# ESP32_With_USB-C_Port_AL.net
KiCad netlist of a schematic drawn in Altium Designer
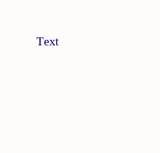
[diagram p0: ESP32_With_USB-C_Port_AL.SchDoc, top left]
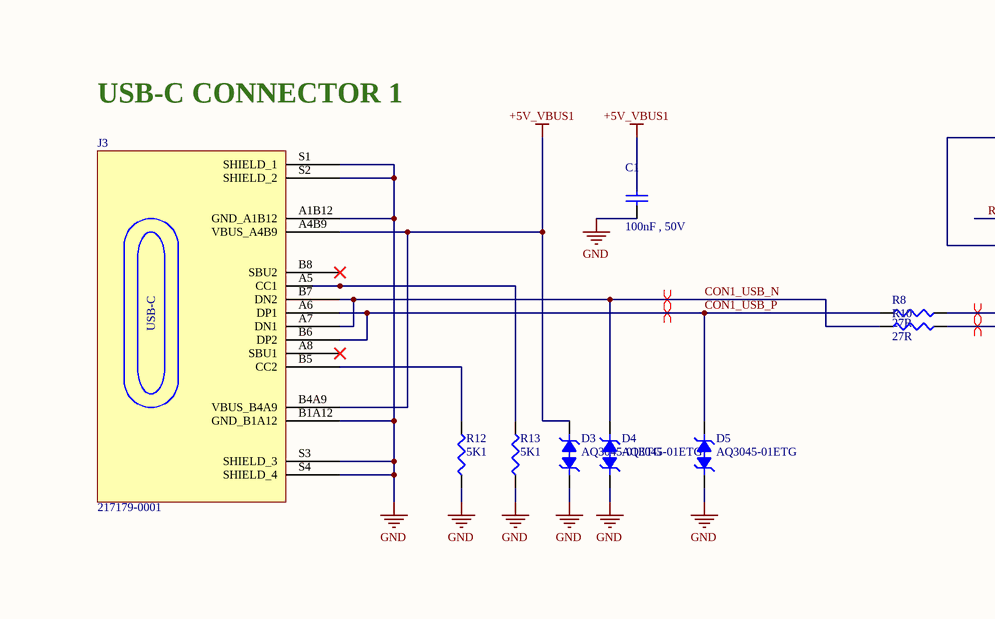
[diagram p1: ESP32_With_USB-C_Port_AL.SchDoc, top middle]
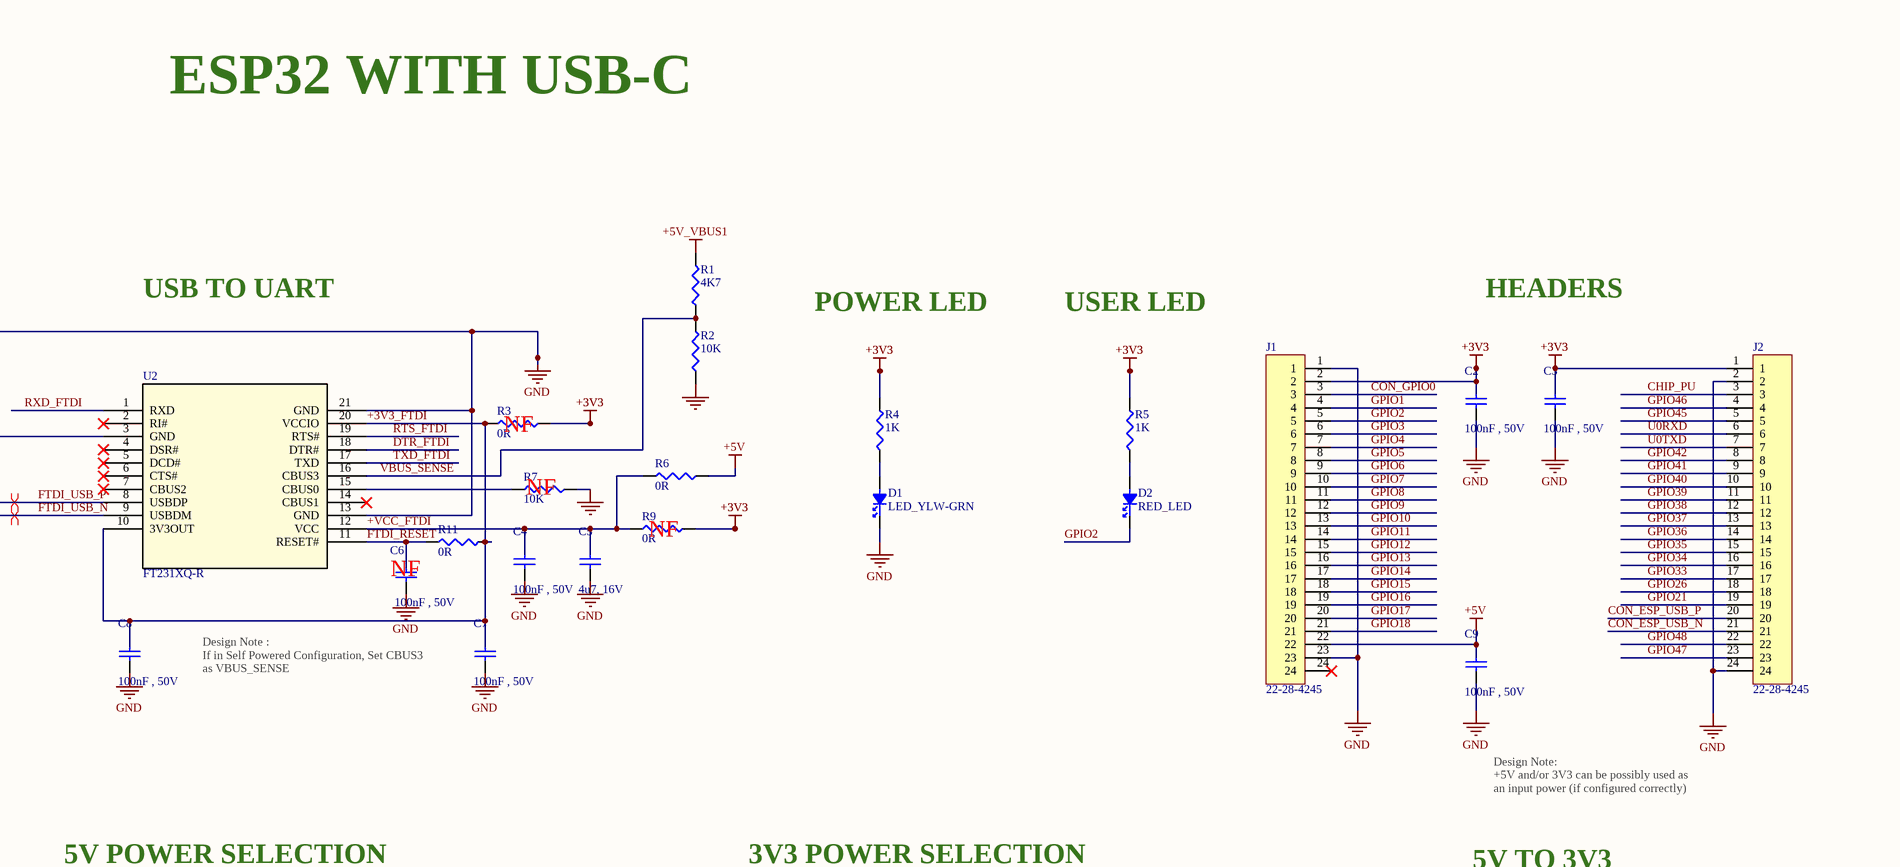
[diagram p2: ESP32_With_USB-C_Port_AL.SchDoc, top right]
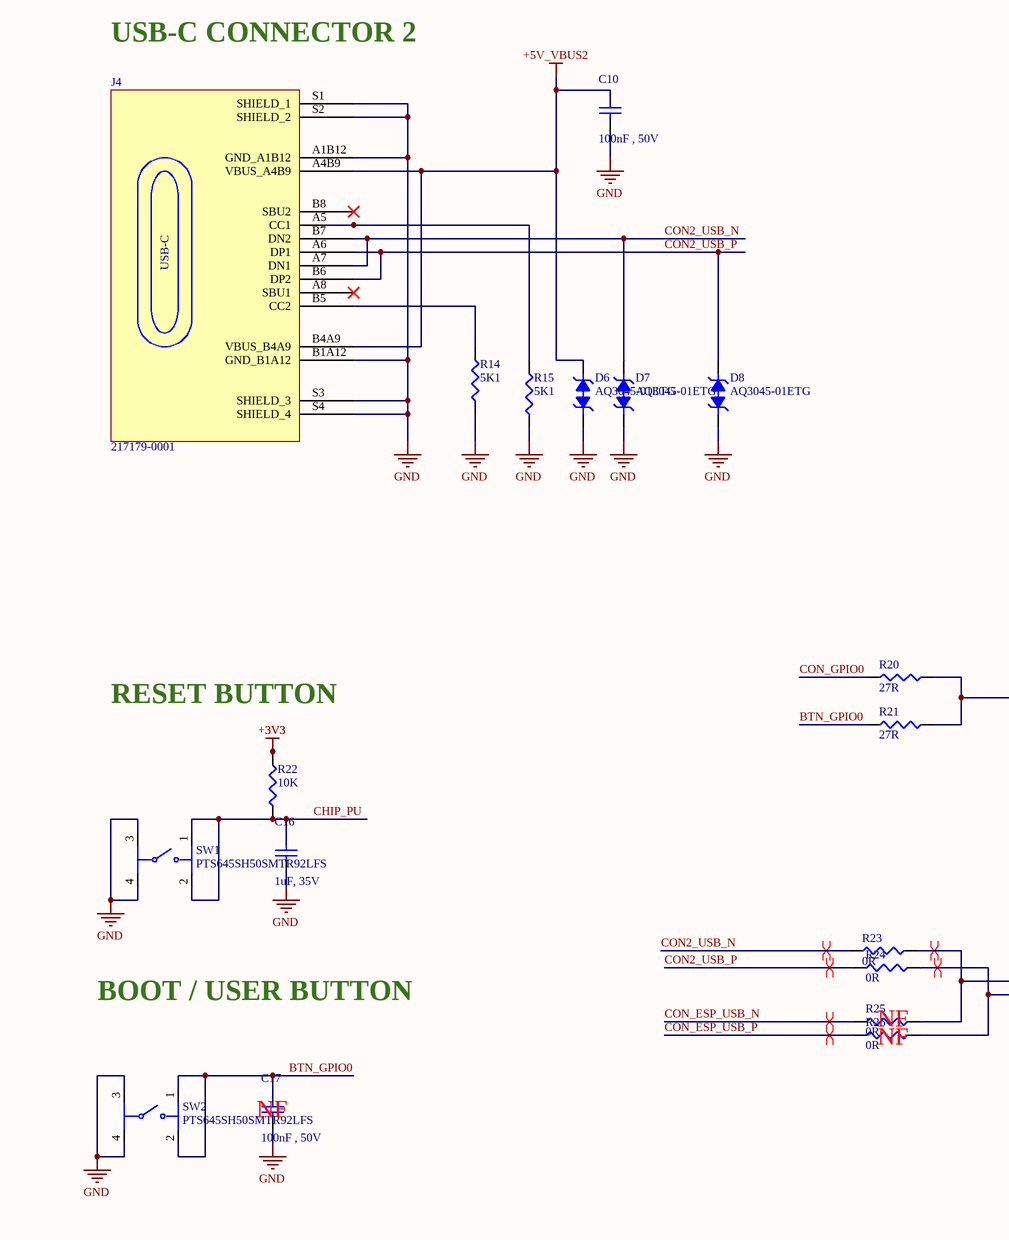
[diagram p3: ESP32_With_USB-C_Port_AL.SchDoc, bottom middle]
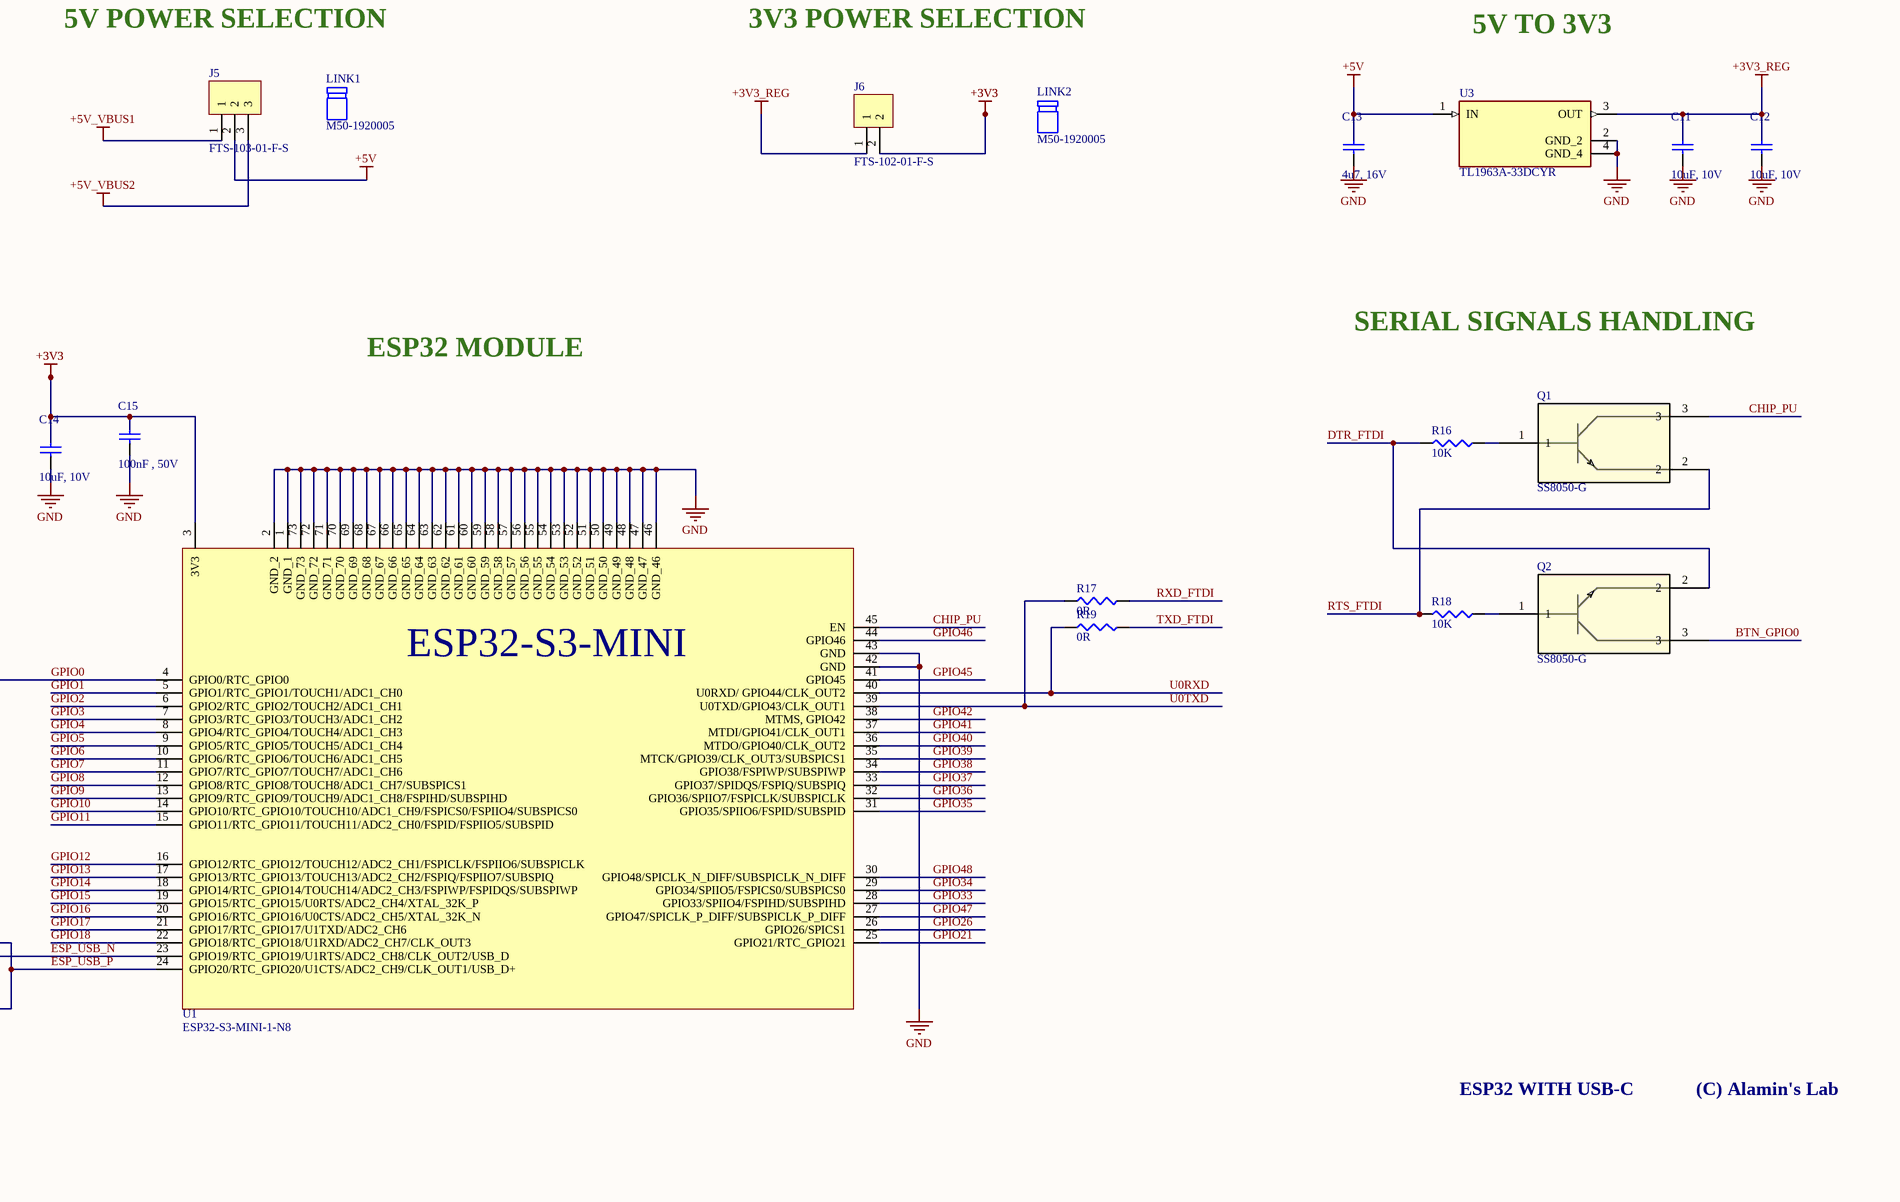
[diagram p4: ESP32_With_USB-C_Port_AL.SchDoc, bottom right]

(export (version "E")
  (design (tool "Eeschema 10.0.6"))
  (components
    (comp (ref "C1")
      (value "100nF , 50V")
      (footprint "CAPC1005X70N_ALL")
      (description "CAP CER 0.1UF 50V X7R 0402")
      (fields
        (field (name "MANUFACTURER") "Samsung")
        (field (name "MANUFACTURER PART NUMBER") "CL05B104KB54PNC")
      )
      (libsource (lib "Schlib1_AL") (part "CL05B104KB54PNC"))
    )
    (comp (ref "C2")
      (value "100nF , 50V")
      (footprint "CAPC1005X70N_ALL")
      (description "CAP CER 0.1UF 50V X7R 0402")
      (fields
        (field (name "MANUFACTURER") "Samsung")
        (field (name "MANUFACTURER PART NUMBER") "CL05B104KB54PNC")
      )
      (libsource (lib "Schlib1_AL") (part "CL05B104KB54PNC"))
    )
    (comp (ref "C3")
      (value "100nF , 50V")
      (footprint "CAPC1005X70N_ALL")
      (description "CAP CER 0.1UF 50V X7R 0402")
      (fields
        (field (name "MANUFACTURER") "Samsung")
        (field (name "MANUFACTURER PART NUMBER") "CL05B104KB54PNC")
      )
      (libsource (lib "Schlib1_AL") (part "CL05B104KB54PNC"))
    )
    (comp (ref "C4")
      (value "100nF , 50V")
      (footprint "CAPC1005X70N_ALL")
      (description "CAP CER 0.1UF 50V X7R 0402")
      (fields
        (field (name "MANUFACTURER") "Samsung")
        (field (name "MANUFACTURER PART NUMBER") "CL05B104KB54PNC")
      )
      (libsource (lib "Schlib1_AL") (part "CL05B104KB54PNC"))
    )
    (comp (ref "C5")
      (value "4u7, 16V")
      (footprint "CAPC1005X70N_ALL")
      (description "CAP CER 4.7UF 16V X5R 0402")
      (fields
        (field (name "MANUFACTURER") "Samsung")
        (field (name "MANUFACTURER PART NUMBER") "CL05A475MO5NUNC")
      )
      (libsource (lib "Schlib1_AL") (part "CL05A475MO5NUNC"))
    )
    (comp (ref "C6")
      (value "100nF , 50V")
      (footprint "CAPC1005X70N_ALL")
      (description "CAP CER 0.1UF 50V X7R 0402")
      (fields
        (field (name "MANUFACTURER") "Samsung")
        (field (name "MANUFACTURER PART NUMBER") "CL05B104KB54PNC")
      )
      (libsource (lib "Schlib1_AL") (part "CL05B104KB54PNC"))
    )
    (comp (ref "C7")
      (value "100nF , 50V")
      (footprint "CAPC1005X70N_ALL")
      (description "CAP CER 0.1UF 50V X7R 0402")
      (fields
        (field (name "MANUFACTURER") "Samsung")
        (field (name "MANUFACTURER PART NUMBER") "CL05B104KB54PNC")
      )
      (libsource (lib "Schlib1_AL") (part "CL05B104KB54PNC"))
    )
    (comp (ref "C8")
      (value "100nF , 50V")
      (footprint "CAPC1005X70N_ALL")
      (description "CAP CER 0.1UF 50V X7R 0402")
      (fields
        (field (name "MANUFACTURER") "Samsung")
        (field (name "MANUFACTURER PART NUMBER") "CL05B104KB54PNC")
      )
      (libsource (lib "Schlib1_AL") (part "CL05B104KB54PNC"))
    )
    (comp (ref "C9")
      (value "100nF , 50V")
      (footprint "CAPC1005X70N_ALL")
      (description "CAP CER 0.1UF 50V X7R 0402")
      (fields
        (field (name "MANUFACTURER") "Samsung")
        (field (name "MANUFACTURER PART NUMBER") "CL05B104KB54PNC")
      )
      (libsource (lib "Schlib1_AL") (part "CL05B104KB54PNC"))
    )
    (comp (ref "C10")
      (value "100nF , 50V")
      (footprint "CAPC1005X70N_ALL")
      (description "CAP CER 0.1UF 50V X7R 0402")
      (fields
        (field (name "MANUFACTURER") "Samsung")
        (field (name "MANUFACTURER PART NUMBER") "CL05B104KB54PNC")
      )
      (libsource (lib "Schlib1_AL") (part "CL05B104KB54PNC"))
    )
    (comp (ref "C11")
      (value "10uF, 10V")
      (footprint "CAPC1005X70N_ALL")
      (description "CAP CER 10UF 10V X5R 0402")
      (fields
        (field (name "MANUFACTURER") "Samsung")
        (field (name "MANUFACTURER PART NUMBER") "CL05A106MP8NUB8")
      )
      (libsource (lib "Schlib1_AL") (part "CL05A106MP8NUB8"))
    )
    (comp (ref "C12")
      (value "10uF, 10V")
      (footprint "CAPC1005X70N_ALL")
      (description "CAP CER 10UF 10V X5R 0402")
      (fields
        (field (name "MANUFACTURER") "Samsung")
        (field (name "MANUFACTURER PART NUMBER") "CL05A106MP8NUB8")
      )
      (libsource (lib "Schlib1_AL") (part "CL05A106MP8NUB8"))
    )
    (comp (ref "C13")
      (value "4u7, 16V")
      (footprint "CAPC1005X70N_ALL")
      (description "CAP CER 4.7UF 16V X5R 0402")
      (fields
        (field (name "MANUFACTURER") "Samsung")
        (field (name "MANUFACTURER PART NUMBER") "CL05A475MO5NUNC")
      )
      (libsource (lib "Schlib1_AL") (part "CL05A475MO5NUNC"))
    )
    (comp (ref "C14")
      (value "10uF, 10V")
      (footprint "CAPC1005X70N_ALL")
      (description "CAP CER 10UF 10V X5R 0402")
      (fields
        (field (name "MANUFACTURER") "Samsung")
        (field (name "MANUFACTURER PART NUMBER") "CL05A106MP8NUB8")
      )
      (libsource (lib "Schlib1_AL") (part "CL05A106MP8NUB8"))
    )
    (comp (ref "C15")
      (value "100nF , 50V")
      (footprint "CAPC1005X70N_ALL")
      (description "CAP CER 0.1UF 50V X7R 0402")
      (fields
        (field (name "MANUFACTURER") "Samsung")
        (field (name "MANUFACTURER PART NUMBER") "CL05B104KB54PNC")
      )
      (libsource (lib "Schlib1_AL") (part "CL05B104KB54PNC"))
    )
    (comp (ref "C16")
      (value "1uF, 35V")
      (footprint "CAPC1005X70N_ALL")
      (description "CAP CER 1UF 35V X5R 0402")
      (fields
        (field (name "MANUFACTURER") "Samsung")
        (field (name "MANUFACTURER PART NUMBER") "CL05A106MP8NUB8")
      )
      (libsource (lib "Schlib1_AL") (part "CL05A106MP8NUB8 (2)"))
    )
    (comp (ref "C17")
      (value "100nF , 50V")
      (footprint "CAPC1005X70N_ALL")
      (description "CAP CER 0.1UF 50V X7R 0402")
      (fields
        (field (name "MANUFACTURER") "Samsung")
        (field (name "MANUFACTURER PART NUMBER") "CL05B104KB54PNC")
      )
      (libsource (lib "Schlib1_AL") (part "CL05B104KB54PNC"))
    )
    (comp (ref "D1")
      (value "LED_YLW-GRN")
      (footprint "LED_0402_YLW_GR")
      (description "LED YLW-GRN 0402 SMD")
      (fields
        (field (name "MANUFACTURER") "Vishay")
        (field (name "MANUFACTURER PART NUMBER") "VLMG1500-GS08")
      )
      (libsource (lib "Schlib1_AL") (part "VLMG1500-GS08"))
    )
    (comp (ref "D2")
      (value "RED_LED")
      (footprint "LED_0402_RED_01- duplicate")
      (description "LED RED 0402 SMD")
      (fields
        (field (name "MANUFACTURER") "Vishay")
        (field (name "MANUFACTURER PART NUMBER") "VLMS1500-GS08")
      )
      (libsource (lib "Schlib1_AL") (part "VLMS1500-GS08"))
    )
    (comp (ref "D3")
      (value "AQ3045-01ETG")
      (footprint "RTVS_SOD882_LTF-M")
      (description "TVS DIODE 5.3VWM 12VC SOD882")
      (fields (field (name "MANUFACTURER") "Littelfuse") (field (name "LCSC PART NUMBER") "C3710326"))
      (libsource (lib "Schlib1_AL") (part "AQ3045-01ETG"))
    )
    (comp (ref "D4")
      (value "AQ3045-01ETG")
      (footprint "RTVS_SOD882_LTF-M")
      (description "TVS DIODE 5.3VWM 12VC SOD882")
      (fields (field (name "MANUFACTURER") "Littelfuse") (field (name "LCSC PART NUMBER") "C3710326"))
      (libsource (lib "Schlib1_AL") (part "AQ3045-01ETG"))
    )
    (comp (ref "D5")
      (value "AQ3045-01ETG")
      (footprint "RTVS_SOD882_LTF-M")
      (description "TVS DIODE 5.3VWM 12VC SOD882")
      (fields (field (name "MANUFACTURER") "Littelfuse") (field (name "LCSC PART NUMBER") "C3710326"))
      (libsource (lib "Schlib1_AL") (part "AQ3045-01ETG"))
    )
    (comp (ref "D6")
      (value "AQ3045-01ETG")
      (footprint "RTVS_SOD882_LTF-M")
      (description "TVS DIODE 5.3VWM 12VC SOD882")
      (fields (field (name "MANUFACTURER") "Littelfuse") (field (name "LCSC PART NUMBER") "C3710326"))
      (libsource (lib "Schlib1_AL") (part "AQ3045-01ETG"))
    )
    (comp (ref "D7")
      (value "AQ3045-01ETG")
      (footprint "RTVS_SOD882_LTF-M")
      (description "TVS DIODE 5.3VWM 12VC SOD882")
      (fields (field (name "MANUFACTURER") "Littelfuse") (field (name "LCSC PART NUMBER") "C3710326"))
      (libsource (lib "Schlib1_AL") (part "AQ3045-01ETG"))
    )
    (comp (ref "D8")
      (value "AQ3045-01ETG")
      (footprint "RTVS_SOD882_LTF-M")
      (description "TVS DIODE 5.3VWM 12VC SOD882")
      (fields (field (name "MANUFACTURER") "Littelfuse") (field (name "LCSC PART NUMBER") "C3710326"))
      (libsource (lib "Schlib1_AL") (part "AQ3045-01ETG"))
    )
    (comp (ref "J1")
      (value "22-28-4245")
      (footprint "CONN_SD-42375-001_M295_24_MOL")
      (description "CONN HEADER VERT 24POS 2.54MM")
      (fields (field (name "MANUFACTURER") "Molex") (field (name "LCSC PART NUMBER") "C7145888"))
      (libsource (lib "Schlib1_AL") (part "22-28-4245"))
    )
    (comp (ref "J2")
      (value "22-28-4245")
      (footprint "CONN_SD-42375-001_M295_24_MOL")
      (description "CONN HEADER VERT 24POS 2.54MM")
      (fields (field (name "MANUFACTURER") "Molex") (field (name "LCSC PART NUMBER") "C7145888"))
      (libsource (lib "") (part "22-28-4245_1"))
    )
    (comp (ref "J3")
      (value "217179-0001")
      (footprint "MOLEX_2171790001")
      (description "CONN RCP USB2.0 TYP C 24P SMD RA")
      (fields (field (name "MANUFACTURER") "Molex") (field (name "LCSC PART NUMBER") "C3197684"))
      (libsource (lib "Schlib1_AL") (part "217179-0001"))
    )
    (comp (ref "J4")
      (value "217179-0001")
      (footprint "MOLEX_2171790001")
      (description "CONN RCP USB2.0 TYP C 24P SMD RA")
      (fields (field (name "MANUFACTURER") "Molex") (field (name "LCSC PART NUMBER") "C3197684"))
      (libsource (lib "Schlib1_AL") (part "217179-0001"))
    )
    (comp (ref "J5")
      (value "FTS-103-01-F-S")
      (footprint "CONN_FTS-103-01-x-S_SAI")
      (description "CONN HEADER VERT 3POS 1.27MM")
      (fields (field (name "MANUFACTURER") "Samtec") (field (name "LCSC PART NUMBER") "C3333578"))
      (libsource (lib "Schlib1_AL") (part "FTS-103-01-F-S"))
    )
    (comp (ref "J6")
      (value "FTS-102-01-F-S")
      (footprint "CONN_FTS-102-01-x-S_SAI")
      (description "CONN HEADER VERT 2POS 1.27MM")
      (fields (field (name "MANUFACTURER") "Samtec") (field (name "LCSC PART NUMBER") "C6045317"))
      (libsource (lib "Schlib1_AL") (part "FTS-102-01-F-S"))
    )
    (comp (ref "LINK1")
      (value "M50-1920005")
      (description "CONN SHUNT 1.27MM RED")
      (fields (field (name "MANUFACTURER") "Harwin") (field (name "LCSC PART NUMBER") "C6985646"))
      (libsource (lib "Schlib1_AL") (part "M50-1920005"))
    )
    (comp (ref "LINK2")
      (value "M50-1920005")
      (description "CONN SHUNT 1.27MM RED")
      (fields (field (name "MANUFACTURER") "Harwin") (field (name "LCSC PART NUMBER") "C6985646"))
      (libsource (lib "Schlib1_AL") (part "M50-1920005"))
    )
    (comp (ref "Q1")
      (value "SS8050-G")
      (footprint "TRAN_SS8050-G_CIP")
      (description "TRANS NPN 25V 1.5A SOT-23-3")
      (fields (field (name "MANUFACTURER") "Comchip") (field (name "LCSC PART NUMBER") "C164886"))
      (libsource (lib "Schlib1_AL") (part "SS8050-G"))
    )
    (comp (ref "Q2")
      (value "SS8050-G")
      (footprint "TRAN_SS8050-G_CIP")
      (description "TRANS NPN 25V 1.5A SOT-23-3")
      (fields (field (name "MANUFACTURER") "Comchip") (field (name "LCSC PART NUMBER") "C164886"))
      (libsource (lib "") (part "SS8050-G_1"))
    )
    (comp (ref "R1")
      (value "4K7")
      (footprint "RESC1005X40N")
      (description "RES 4.7K OHM 1% 1/16W 0402")
      (fields
        (field (name "MANUFACTURER") "Yageo")
        (field (name "MANUFACTURER PART NUMBER") "RC0402FR-074K7L")
      )
      (libsource (lib "Schlib1_AL") (part "RC0402FR-074K7L"))
    )
    (comp (ref "R2")
      (value "10K")
      (footprint "RESC1005X37N_10k")
      (description "RES SMD 10K OHM 1% 1/16W 0402")
      (fields
        (field (name "MANUFACTURER") "Yageo")
        (field (name "MANUFACTURER PART NUMBER") "AC0402FR-0710KL")
      )
      (libsource (lib "Schlib1_AL") (part "AC0402FR-0710KL"))
    )
    (comp (ref "R3")
      (value "0R")
      (footprint "RESC1005X40_0")
      (description "RES 0 OHM JUMPER 1/16W 0402")
      (fields
        (field (name "MANUFACTURER") "Yageo")
        (field (name "MANUFACTURER PART NUMBER") "RC0402JR-070RL")
      )
      (libsource (lib "Schlib1_AL") (part "RC0402JR-070RL"))
    )
    (comp (ref "R4")
      (value "1K")
      (footprint "RESC1005X40N_1k")
      (description "RES 1K OHM 1% 1/16W 0402")
      (fields
        (field (name "MANUFACTURER") "Yageo")
        (field (name "MANUFACTURER PART NUMBER") "RC0402FR-071KL")
      )
      (libsource (lib "Schlib1_AL") (part "RC0402FR-071KL"))
    )
    (comp (ref "R5")
      (value "1K")
      (footprint "RESC1005X40N_1k")
      (description "RES 1K OHM 1% 1/16W 0402")
      (fields
        (field (name "MANUFACTURER") "Yageo")
        (field (name "MANUFACTURER PART NUMBER") "RC0402FR-071KL")
      )
      (libsource (lib "Schlib1_AL") (part "RC0402FR-071KL"))
    )
    (comp (ref "R6")
      (value "0R")
      (footprint "RESC1005X40_0")
      (description "RES 0 OHM JUMPER 1/16W 0402")
      (fields
        (field (name "MANUFACTURER") "Yageo")
        (field (name "MANUFACTURER PART NUMBER") "RC0402JR-070RL")
      )
      (libsource (lib "Schlib1_AL") (part "RC0402JR-070RL"))
    )
    (comp (ref "R7")
      (value "10K")
      (footprint "RESC1005X37N_10k")
      (description "RES SMD 10K OHM 1% 1/16W 0402")
      (fields
        (field (name "MANUFACTURER") "Yageo")
        (field (name "MANUFACTURER PART NUMBER") "AC0402FR-0710KL")
      )
      (libsource (lib "Schlib1_AL") (part "AC0402FR-0710KL"))
    )
    (comp (ref "R8")
      (value "27R")
      (footprint "RESC1005X40N_27")
      (description "RES 27 OHM 1% 1/16W 0402")
      (fields
        (field (name "MANUFACTURER") "Yageo")
        (field (name "MANUFACTURER PART NUMBER") "RC0402FR-0727RL")
      )
      (libsource (lib "Schlib1_AL") (part "RC0402FR-0727RL"))
    )
    (comp (ref "R9")
      (value "0R")
      (footprint "RESC1005X40_0")
      (description "RES 0 OHM JUMPER 1/16W 0402")
      (fields
        (field (name "MANUFACTURER") "Yageo")
        (field (name "MANUFACTURER PART NUMBER") "RC0402JR-070RL")
      )
      (libsource (lib "Schlib1_AL") (part "RC0402JR-070RL"))
    )
    (comp (ref "R10")
      (value "27R")
      (footprint "RESC1005X40N_27")
      (description "RES 27 OHM 1% 1/16W 0402")
      (fields
        (field (name "MANUFACTURER") "Yageo")
        (field (name "MANUFACTURER PART NUMBER") "RC0402FR-0727RL")
      )
      (libsource (lib "Schlib1_AL") (part "RC0402FR-0727RL"))
    )
    (comp (ref "R11")
      (value "0R")
      (footprint "RESC1005X40_0")
      (description "RES 0 OHM JUMPER 1/16W 0402")
      (fields
        (field (name "MANUFACTURER") "Yageo")
        (field (name "MANUFACTURER PART NUMBER") "RC0402JR-070RL")
      )
      (libsource (lib "Schlib1_AL") (part "RC0402JR-070RL"))
    )
    (comp (ref "R12")
      (value "5K1")
      (footprint "RESC1005X37N_5.1")
      (description "RES SMD 5.1K OHM 1% 1/16W 0402")
      (fields
        (field (name "MANUFACTURER") "Yageo")
        (field (name "MANUFACTURER PART NUMBER") "AC0402FR-075K1L")
      )
      (libsource (lib "Schlib1_AL") (part "AC0402FR-075K1L"))
    )
    (comp (ref "R13")
      (value "5K1")
      (footprint "RESC1005X37N_5.1")
      (description "RES SMD 5.1K OHM 1% 1/16W 0402")
      (fields
        (field (name "MANUFACTURER") "Yageo")
        (field (name "MANUFACTURER PART NUMBER") "AC0402FR-075K1L")
      )
      (libsource (lib "Schlib1_AL") (part "AC0402FR-075K1L"))
    )
    (comp (ref "R14")
      (value "5K1")
      (footprint "RESC1005X37N_5.1")
      (description "RES SMD 5.1K OHM 1% 1/16W 0402")
      (fields
        (field (name "MANUFACTURER") "Yageo")
        (field (name "MANUFACTURER PART NUMBER") "AC0402FR-075K1L")
      )
      (libsource (lib "Schlib1_AL") (part "AC0402FR-075K1L"))
    )
    (comp (ref "R15")
      (value "5K1")
      (footprint "RESC1005X37N_5.1")
      (description "RES SMD 5.1K OHM 1% 1/16W 0402")
      (fields
        (field (name "MANUFACTURER") "Yageo")
        (field (name "MANUFACTURER PART NUMBER") "AC0402FR-075K1L")
      )
      (libsource (lib "Schlib1_AL") (part "AC0402FR-075K1L"))
    )
    (comp (ref "R16")
      (value "10K")
      (footprint "RESC1005X37N_10k")
      (description "RES SMD 10K OHM 1% 1/16W 0402")
      (fields
        (field (name "MANUFACTURER") "Yageo")
        (field (name "MANUFACTURER PART NUMBER") "AC0402FR-0710KL")
      )
      (libsource (lib "Schlib1_AL") (part "AC0402FR-0710KL"))
    )
    (comp (ref "R17")
      (value "0R")
      (footprint "RESC1005X40_0")
      (description "RES 0 OHM JUMPER 1/16W 0402")
      (fields
        (field (name "MANUFACTURER") "Yageo")
        (field (name "MANUFACTURER PART NUMBER") "RC0402JR-070RL")
      )
      (libsource (lib "Schlib1_AL") (part "RC0402JR-070RL"))
    )
    (comp (ref "R18")
      (value "10K")
      (footprint "RESC1005X37N_10k")
      (description "RES SMD 10K OHM 1% 1/16W 0402")
      (fields
        (field (name "MANUFACTURER") "Yageo")
        (field (name "MANUFACTURER PART NUMBER") "AC0402FR-0710KL")
      )
      (libsource (lib "Schlib1_AL") (part "AC0402FR-0710KL"))
    )
    (comp (ref "R19")
      (value "0R")
      (footprint "RESC1005X40_0")
      (description "RES 0 OHM JUMPER 1/16W 0402")
      (fields
        (field (name "MANUFACTURER") "Yageo")
        (field (name "MANUFACTURER PART NUMBER") "RC0402JR-070RL")
      )
      (libsource (lib "Schlib1_AL") (part "RC0402JR-070RL"))
    )
    (comp (ref "R20")
      (value "27R")
      (footprint "RESC1005X40N_27")
      (description "RES 27 OHM 1% 1/16W 0402")
      (fields
        (field (name "MANUFACTURER") "Yageo")
        (field (name "MANUFACTURER PART NUMBER") "RC0402FR-0727RL")
      )
      (libsource (lib "Schlib1_AL") (part "RC0402FR-0727RL"))
    )
    (comp (ref "R21")
      (value "27R")
      (footprint "RESC1005X40N_27")
      (description "RES 27 OHM 1% 1/16W 0402")
      (fields
        (field (name "MANUFACTURER") "Yageo")
        (field (name "MANUFACTURER PART NUMBER") "RC0402FR-0727RL")
      )
      (libsource (lib "Schlib1_AL") (part "RC0402FR-0727RL"))
    )
    (comp (ref "R22")
      (value "10K")
      (footprint "RESC1005X37N_10k")
      (description "RES SMD 10K OHM 1% 1/16W 0402")
      (fields
        (field (name "MANUFACTURER") "Yageo")
        (field (name "MANUFACTURER PART NUMBER") "AC0402FR-0710KL")
      )
      (libsource (lib "Schlib1_AL") (part "AC0402FR-0710KL"))
    )
    (comp (ref "R23")
      (value "0R")
      (footprint "RESC1005X40_0")
      (description "RES 0 OHM JUMPER 1/16W 0402")
      (fields
        (field (name "MANUFACTURER") "Yageo")
        (field (name "MANUFACTURER PART NUMBER") "RC0402JR-070RL")
      )
      (libsource (lib "Schlib1_AL") (part "RC0402JR-070RL"))
    )
    (comp (ref "R24")
      (value "0R")
      (footprint "RESC1005X40_0")
      (description "RES 0 OHM JUMPER 1/16W 0402")
      (fields
        (field (name "MANUFACTURER") "Yageo")
        (field (name "MANUFACTURER PART NUMBER") "RC0402JR-070RL")
      )
      (libsource (lib "Schlib1_AL") (part "RC0402JR-070RL"))
    )
    (comp (ref "R25")
      (value "0R")
      (footprint "RESC1005X40_0")
      (description "RES 0 OHM JUMPER 1/16W 0402")
      (fields
        (field (name "MANUFACTURER") "Yageo")
        (field (name "MANUFACTURER PART NUMBER") "RC0402JR-070RL")
      )
      (libsource (lib "Schlib1_AL") (part "RC0402JR-070RL"))
    )
    (comp (ref "R26")
      (value "0R")
      (footprint "RESC1005X40_0")
      (description "RES 0 OHM JUMPER 1/16W 0402")
      (fields
        (field (name "MANUFACTURER") "Yageo")
        (field (name "MANUFACTURER PART NUMBER") "RC0402JR-070RL")
      )
      (libsource (lib "Schlib1_AL") (part "RC0402JR-070RL"))
    )
    (comp (ref "SW1")
      (value "PTS645SH50SMTR92LFS")
      (footprint "PTS645S_SMTR92_CNK")
      (description "SWITCH TACTILE SPST-NO 0.05A 12V")
      (fields (field (name "MANUFACTURER") "ITT C&K") (field (name "LCSC PART NUMBER") "C221869"))
      (libsource (lib "Schlib1_AL") (part "PTS645SH50SMTR92LFS"))
    )
    (comp (ref "SW2")
      (value "PTS645SH50SMTR92LFS")
      (footprint "PTS645S_SMTR92_CNK")
      (description "SWITCH TACTILE SPST-NO 0.05A 12V")
      (fields (field (name "MANUFACTURER") "ITT C&K") (field (name "LCSC PART NUMBER") "C221869"))
      (libsource (lib "Schlib1_AL") (part "PTS645SH50SMTR92LFS"))
    )
    (comp (ref "U1")
      (value "ESP32-S3-MINI-1-N8")
      (footprint "XCVR_ESP32-S3-MINI-1-N8")
      (description "SMD module, ESP32-S3FN8, 8 MB SPI flash, PCB antenna")
      (fields (field (name "MANUFACTURER") "Espressif Systems") (field (name "LCSC PART NUMBER") "C2913206"))
      (libsource (lib "Schlib1_AL") (part "ESP32-S3-MINI-1-N8"))
    )
    (comp (ref "U2")
      (value "FT231XQ-R")
      (footprint "QFN20_FT231XQ_FTD-M")
      (description "IC USB SERIAL FULL UART 20QFN")
      (fields (field (name "MANUFACTURER") "FTDI") (field (name "LCSC PART NUMBER") "C132159"))
      (libsource (lib "Schlib1_AL") (part "FT231XQ-R"))
    )
    (comp (ref "U3")
      (value "TL1963A-33DCYR")
      (footprint "VREG_TL1963A-33DCYR")
      (description "IC REG LIN 3.3V 1.5A SOT-223-4")
      (fields (field (name "MANUFACTURER") "Texas Instruments") (field (name "LCSC PART NUMBER") "C181262"))
      (libsource (lib "Schlib1_AL") (part "TL1963A-33DCYR"))
    )
  )
  (nets
    (net (code "1") (name "+3V3") (class "Default")
      (node (ref "C14") (pin "2") (pinfunction "2_2") (pintype "passive"))
      (node (ref "C15") (pin "2") (pinfunction "2_2") (pintype "passive"))
      (node (ref "C2") (pin "2") (pinfunction "2_2") (pintype "passive"))
      (node (ref "C3") (pin "2") (pinfunction "2_2") (pintype "passive"))
      (node (ref "J1") (pin "2") (pinfunction "2_2") (pintype "passive"))
      (node (ref "J2") (pin "1") (pinfunction "1_1") (pintype "passive"))
      (node (ref "J6") (pin "2") (pinfunction "2_2") (pintype "passive"))
      (node (ref "R22") (pin "2") (pinfunction "2_2") (pintype "passive"))
      (node (ref "R3") (pin "2") (pinfunction "2_2") (pintype "passive"))
      (node (ref "R4") (pin "2") (pinfunction "2_2") (pintype "passive"))
      (node (ref "R5") (pin "2") (pinfunction "2_2") (pintype "passive"))
      (node (ref "R9") (pin "2") (pinfunction "2_2") (pintype "passive"))
      (node (ref "U1") (pin "3") (pinfunction "3V3_3") (pintype "passive"))
    )
    (net (code "2") (name "+3V3_REG") (class "Default")
      (node (ref "C11") (pin "2") (pinfunction "2_2") (pintype "passive"))
      (node (ref "C12") (pin "2") (pinfunction "2_2") (pintype "passive"))
      (node (ref "J6") (pin "1") (pinfunction "1_1") (pintype "passive"))
      (node (ref "U3") (pin "3") (pinfunction "OUT_3") (pintype "output"))
    )
    (net (code "3") (name "+5V") (class "Default")
      (node (ref "C13") (pin "2") (pinfunction "2_2") (pintype "passive"))
      (node (ref "C9") (pin "2") (pinfunction "2_2") (pintype "passive"))
      (node (ref "J1") (pin "22") (pinfunction "22_22") (pintype "passive"))
      (node (ref "J5") (pin "2") (pinfunction "2_2") (pintype "passive"))
      (node (ref "R6") (pin "2") (pinfunction "2_2") (pintype "passive"))
      (node (ref "U3") (pin "1") (pinfunction "IN_1") (pintype "input"))
    )
    (net (code "4") (name "+5V_VBUS1") (class "Default")
      (node (ref "C1") (pin "2") (pinfunction "2_2") (pintype "passive"))
      (node (ref "D3") (pin "2") (pinfunction "2_2") (pintype "passive"))
      (node (ref "J3") (pin "A4B9") (pinfunction "VBUS_A4B9_A4B9") (pintype "passive"))
      (node (ref "J3") (pin "B4A9") (pinfunction "VBUS_B4A9_B4A9") (pintype "passive"))
      (node (ref "J5") (pin "1") (pinfunction "1_1") (pintype "passive"))
      (node (ref "R1") (pin "2") (pinfunction "2_2") (pintype "passive"))
    )
    (net (code "5") (name "+5V_VBUS2") (class "Default")
      (node (ref "C10") (pin "2") (pinfunction "2_2") (pintype "passive"))
      (node (ref "D6") (pin "2") (pinfunction "2_2") (pintype "passive"))
      (node (ref "J4") (pin "A4B9") (pinfunction "VBUS_A4B9_A4B9") (pintype "passive"))
      (node (ref "J4") (pin "B4A9") (pinfunction "VBUS_B4A9_B4A9") (pintype "passive"))
      (node (ref "J5") (pin "3") (pinfunction "3_3") (pintype "passive"))
    )
    (net (code "6") (name "/+3V3_FTDI") (class "Default")
      (node (ref "C7") (pin "2") (pinfunction "2_2") (pintype "passive"))
      (node (ref "C8") (pin "2") (pinfunction "2_2") (pintype "passive"))
      (node (ref "R11") (pin "1") (pinfunction "1_1") (pintype "passive"))
      (node (ref "R3") (pin "1") (pinfunction "1_1") (pintype "passive"))
      (node (ref "U2") (pin "10") (pinfunction "3V3OUT_10") (pintype "passive"))
      (node (ref "U2") (pin "20") (pinfunction "VCCIO_20") (pintype "passive"))
    )
    (net (code "7") (name "/+VCC_FTDI") (class "Default")
      (node (ref "C4") (pin "2") (pinfunction "2_2") (pintype "passive"))
      (node (ref "C5") (pin "2") (pinfunction "2_2") (pintype "passive"))
      (node (ref "R6") (pin "1") (pinfunction "1_1") (pintype "passive"))
      (node (ref "R9") (pin "1") (pinfunction "1_1") (pintype "passive"))
      (node (ref "U2") (pin "12") (pinfunction "VCC_12") (pintype "passive"))
    )
    (net (code "8") (name "/BTN_GPIO0") (class "Default")
      (node (ref "C17") (pin "2") (pinfunction "2_2") (pintype "passive"))
      (node (ref "Q2") (pin "3") (pinfunction "3_3") (pintype "passive"))
      (node (ref "R21") (pin "1") (pinfunction "1_1") (pintype "passive"))
      (node (ref "SW2") (pin "1") (pinfunction "1_1") (pintype "passive"))
      (node (ref "SW2") (pin "2") (pinfunction "2_2") (pintype "passive"))
    )
    (net (code "9") (name "/CHIP_PU") (class "Default")
      (node (ref "C16") (pin "2") (pinfunction "2_2") (pintype "passive"))
      (node (ref "J2") (pin "3") (pinfunction "3_3") (pintype "passive"))
      (node (ref "Q1") (pin "3") (pinfunction "3_3") (pintype "passive"))
      (node (ref "R22") (pin "1") (pinfunction "1_1") (pintype "passive"))
      (node (ref "SW1") (pin "1") (pinfunction "1_1") (pintype "passive"))
      (node (ref "SW1") (pin "2") (pinfunction "2_2") (pintype "passive"))
      (node (ref "U1") (pin "45") (pinfunction "EN_45") (pintype "passive"))
    )
    (net (code "10") (name "/CON1_USB_N") (class "Default")
      (node (ref "D4") (pin "2") (pinfunction "2_2") (pintype "passive"))
      (node (ref "J3") (pin "A7") (pinfunction "DN1_A7") (pintype "passive"))
      (node (ref "J3") (pin "B7") (pinfunction "DN2_B7") (pintype "passive"))
      (node (ref "R10") (pin "1") (pinfunction "1_1") (pintype "passive"))
    )
    (net (code "11") (name "/CON1_USB_P") (class "Default")
      (node (ref "D5") (pin "2") (pinfunction "2_2") (pintype "passive"))
      (node (ref "J3") (pin "A6") (pinfunction "DP1_A6") (pintype "passive"))
      (node (ref "J3") (pin "B6") (pinfunction "DP2_B6") (pintype "passive"))
      (node (ref "R8") (pin "1") (pinfunction "1_1") (pintype "passive"))
    )
    (net (code "12") (name "/CON2_USB_N") (class "Default")
      (node (ref "D7") (pin "2") (pinfunction "2_2") (pintype "passive"))
      (node (ref "J4") (pin "A7") (pinfunction "DN1_A7") (pintype "passive"))
      (node (ref "J4") (pin "B7") (pinfunction "DN2_B7") (pintype "passive"))
      (node (ref "R23") (pin "1") (pinfunction "1_1") (pintype "passive"))
    )
    (net (code "13") (name "/CON2_USB_P") (class "Default")
      (node (ref "D8") (pin "2") (pinfunction "2_2") (pintype "passive"))
      (node (ref "J4") (pin "A6") (pinfunction "DP1_A6") (pintype "passive"))
      (node (ref "J4") (pin "B6") (pinfunction "DP2_B6") (pintype "passive"))
      (node (ref "R24") (pin "1") (pinfunction "1_1") (pintype "passive"))
    )
    (net (code "14") (name "/CON_ESP_USB_N") (class "Default")
      (node (ref "J2") (pin "21") (pinfunction "21_21") (pintype "passive"))
      (node (ref "R25") (pin "1") (pinfunction "1_1") (pintype "passive"))
    )
    (net (code "15") (name "/CON_ESP_USB_P") (class "Default")
      (node (ref "J2") (pin "20") (pinfunction "20_20") (pintype "passive"))
      (node (ref "R26") (pin "1") (pinfunction "1_1") (pintype "passive"))
    )
    (net (code "16") (name "/CON_GPIO0") (class "Default")
      (node (ref "J1") (pin "3") (pinfunction "3_3") (pintype "passive"))
      (node (ref "R20") (pin "1") (pinfunction "1_1") (pintype "passive"))
    )
    (net (code "17") (name "/DTR_FTDI") (class "Default")
      (node (ref "Q2") (pin "2") (pinfunction "2_2") (pintype "passive"))
      (node (ref "R16") (pin "2") (pinfunction "2_2") (pintype "passive"))
      (node (ref "U2") (pin "18") (pinfunction "DTR#_18") (pintype "passive"))
    )
    (net (code "18") (name "/ESP_USB_N") (class "Default")
      (node (ref "R23") (pin "2") (pinfunction "2_2") (pintype "passive"))
      (node (ref "R25") (pin "2") (pinfunction "2_2") (pintype "passive"))
      (node (ref "U1") (pin "23") (pinfunction "GPIO19/RTC_GPIO19/U1RTS/ADC2_CH8/CLK_OUT2/USB_D_23") (pintype "passive"))
    )
    (net (code "19") (name "/ESP_USB_P") (class "Default")
      (node (ref "R24") (pin "2") (pinfunction "2_2") (pintype "passive"))
      (node (ref "R26") (pin "2") (pinfunction "2_2") (pintype "passive"))
      (node (ref "U1") (pin "24") (pinfunction "GPIO20/RTC_GPIO20/U1CTS/ADC2_CH9/CLK_OUT1/USB_D+_24") (pintype "passive"))
    )
    (net (code "20") (name "/FTDI_RESET") (class "Default")
      (node (ref "C6") (pin "2") (pinfunction "2_2") (pintype "passive"))
      (node (ref "R11") (pin "2") (pinfunction "2_2") (pintype "passive"))
      (node (ref "U2") (pin "11") (pinfunction "RESET#_11") (pintype "passive"))
    )
    (net (code "21") (name "/FTDI_USB_N") (class "Default")
      (node (ref "R10") (pin "2") (pinfunction "2_2") (pintype "passive"))
      (node (ref "U2") (pin "9") (pinfunction "USBDM_9") (pintype "passive"))
    )
    (net (code "22") (name "/FTDI_USB_P") (class "Default")
      (node (ref "R8") (pin "2") (pinfunction "2_2") (pintype "passive"))
      (node (ref "U2") (pin "8") (pinfunction "USBDP_8") (pintype "passive"))
    )
    (net (code "23") (name "/GPIO0") (class "Default")
      (node (ref "R20") (pin "2") (pinfunction "2_2") (pintype "passive"))
      (node (ref "R21") (pin "2") (pinfunction "2_2") (pintype "passive"))
      (node (ref "U1") (pin "4") (pinfunction "GPIO0/RTC_GPIO0_4") (pintype "passive"))
    )
    (net (code "24") (name "/GPIO1") (class "Default")
      (node (ref "J1") (pin "4") (pinfunction "4_4") (pintype "passive"))
      (node (ref "U1") (pin "5") (pinfunction "GPIO1/RTC_GPIO1/TOUCH1/ADC1_CH0_5") (pintype "passive"))
    )
    (net (code "25") (name "/GPIO2") (class "Default")
      (node (ref "D2") (pin "1") (pinfunction "1_1") (pintype "passive"))
      (node (ref "J1") (pin "5") (pinfunction "5_5") (pintype "passive"))
      (node (ref "U1") (pin "6") (pinfunction "GPIO2/RTC_GPIO2/TOUCH2/ADC1_CH1_6") (pintype "passive"))
    )
    (net (code "26") (name "/GPIO3") (class "Default")
      (node (ref "J1") (pin "6") (pinfunction "6_6") (pintype "passive"))
      (node (ref "U1") (pin "7") (pinfunction "GPIO3/RTC_GPIO3/TOUCH3/ADC1_CH2_7") (pintype "passive"))
    )
    (net (code "27") (name "/GPIO4") (class "Default")
      (node (ref "J1") (pin "7") (pinfunction "7_7") (pintype "passive"))
      (node (ref "U1") (pin "8") (pinfunction "GPIO4/RTC_GPIO4/TOUCH4/ADC1_CH3_8") (pintype "passive"))
    )
    (net (code "28") (name "/GPIO5") (class "Default")
      (node (ref "J1") (pin "8") (pinfunction "8_8") (pintype "passive"))
      (node (ref "U1") (pin "9") (pinfunction "GPIO5/RTC_GPIO5/TOUCH5/ADC1_CH4_9") (pintype "passive"))
    )
    (net (code "29") (name "/GPIO6") (class "Default")
      (node (ref "J1") (pin "9") (pinfunction "9_9") (pintype "passive"))
      (node (ref "U1") (pin "10") (pinfunction "GPIO6/RTC_GPIO6/TOUCH6/ADC1_CH5_10") (pintype "passive"))
    )
    (net (code "30") (name "/GPIO7") (class "Default")
      (node (ref "J1") (pin "10") (pinfunction "10_10") (pintype "passive"))
      (node (ref "U1") (pin "11") (pinfunction "GPIO7/RTC_GPIO7/TOUCH7/ADC1_CH6_11") (pintype "passive"))
    )
    (net (code "31") (name "/GPIO8") (class "Default")
      (node (ref "J1") (pin "11") (pinfunction "11_11") (pintype "passive"))
      (node (ref "U1") (pin "12") (pinfunction "GPIO8/RTC_GPIO8/TOUCH8/ADC1_CH7/SUBSPICS1_12") (pintype "passive"))
    )
    (net (code "32") (name "/GPIO9") (class "Default")
      (node (ref "J1") (pin "12") (pinfunction "12_12") (pintype "passive"))
      (node (ref "U1") (pin "13") (pinfunction "GPIO9/RTC_GPIO9/TOUCH9/ADC1_CH8/FSPIHD/SUBSPIHD_13") (pintype "passive"))
    )
    (net (code "33") (name "/GPIO10") (class "Default")
      (node (ref "J1") (pin "13") (pinfunction "13_13") (pintype "passive"))
      (node (ref "U1") (pin "14") (pinfunction "GPIO10/RTC_GPIO10/TOUCH10/ADC1_CH9/FSPICS0/FSPIIO4/SUBSPICS0_14") (pintype "passive"))
    )
    (net (code "34") (name "/GPIO11") (class "Default")
      (node (ref "J1") (pin "14") (pinfunction "14_14") (pintype "passive"))
      (node (ref "U1") (pin "15") (pinfunction "GPIO11/RTC_GPIO11/TOUCH11/ADC2_CH0/FSPID/FSPIIO5/SUBSPID_15") (pintype "passive"))
    )
    (net (code "35") (name "/GPIO12") (class "Default")
      (node (ref "J1") (pin "15") (pinfunction "15_15") (pintype "passive"))
      (node (ref "U1") (pin "16") (pinfunction "GPIO12/RTC_GPIO12/TOUCH12/ADC2_CH1/FSPICLK/FSPIIO6/SUBSPICLK_16") (pintype "passive"))
    )
    (net (code "36") (name "/GPIO13") (class "Default")
      (node (ref "J1") (pin "16") (pinfunction "16_16") (pintype "passive"))
      (node (ref "U1") (pin "17") (pinfunction "GPIO13/RTC_GPIO13/TOUCH13/ADC2_CH2/FSPIQ/FSPIIO7/SUBSPIQ_17") (pintype "passive"))
    )
    (net (code "37") (name "/GPIO14") (class "Default")
      (node (ref "J1") (pin "17") (pinfunction "17_17") (pintype "passive"))
      (node (ref "U1") (pin "18") (pinfunction "GPIO14/RTC_GPIO14/TOUCH14/ADC2_CH3/FSPIWP/FSPIDQS/SUBSPIWP_18") (pintype "passive"))
    )
    (net (code "38") (name "/GPIO15") (class "Default")
      (node (ref "J1") (pin "18") (pinfunction "18_18") (pintype "passive"))
      (node (ref "U1") (pin "19") (pinfunction "GPIO15/RTC_GPIO15/U0RTS/ADC2_CH4/XTAL_32K_P_19") (pintype "passive"))
    )
    (net (code "39") (name "/GPIO16") (class "Default")
      (node (ref "J1") (pin "19") (pinfunction "19_19") (pintype "passive"))
      (node (ref "U1") (pin "20") (pinfunction "GPIO16/RTC_GPIO16/U0CTS/ADC2_CH5/XTAL_32K_N_20") (pintype "passive"))
    )
    (net (code "40") (name "/GPIO17") (class "Default")
      (node (ref "J1") (pin "20") (pinfunction "20_20") (pintype "passive"))
      (node (ref "U1") (pin "21") (pinfunction "GPIO17/RTC_GPIO17/U1TXD/ADC2_CH6_21") (pintype "passive"))
    )
    (net (code "41") (name "/GPIO18") (class "Default")
      (node (ref "J1") (pin "21") (pinfunction "21_21") (pintype "passive"))
      (node (ref "U1") (pin "22") (pinfunction "GPIO18/RTC_GPIO18/U1RXD/ADC2_CH7/CLK_OUT3_22") (pintype "passive"))
    )
    (net (code "42") (name "/GPIO21") (class "Default")
      (node (ref "J2") (pin "19") (pinfunction "19_19") (pintype "passive"))
      (node (ref "U1") (pin "25") (pinfunction "GPIO21/RTC_GPIO21_25") (pintype "passive"))
    )
    (net (code "43") (name "/GPIO26") (class "Default")
      (node (ref "J2") (pin "18") (pinfunction "18_18") (pintype "passive"))
      (node (ref "U1") (pin "26") (pinfunction "GPIO26/SPICS1_26") (pintype "passive"))
    )
    (net (code "44") (name "/GPIO33") (class "Default")
      (node (ref "J2") (pin "17") (pinfunction "17_17") (pintype "passive"))
      (node (ref "U1") (pin "28") (pinfunction "GPIO33/SPIIO4/FSPIHD/SUBSPIHD_28") (pintype "passive"))
    )
    (net (code "45") (name "/GPIO34") (class "Default")
      (node (ref "J2") (pin "16") (pinfunction "16_16") (pintype "passive"))
      (node (ref "U1") (pin "29") (pinfunction "GPIO34/SPIIO5/FSPICS0/SUBSPICS0_29") (pintype "passive"))
    )
    (net (code "46") (name "/GPIO35") (class "Default")
      (node (ref "J2") (pin "15") (pinfunction "15_15") (pintype "passive"))
      (node (ref "U1") (pin "31") (pinfunction "GPIO35/SPIIO6/FSPID/SUBSPID_31") (pintype "passive"))
    )
    (net (code "47") (name "/GPIO36") (class "Default")
      (node (ref "J2") (pin "14") (pinfunction "14_14") (pintype "passive"))
      (node (ref "U1") (pin "32") (pinfunction "GPIO36/SPIIO7/FSPICLK/SUBSPICLK_32") (pintype "passive"))
    )
    (net (code "48") (name "/GPIO37") (class "Default")
      (node (ref "J2") (pin "13") (pinfunction "13_13") (pintype "passive"))
      (node (ref "U1") (pin "33") (pinfunction "GPIO37/SPIDQS/FSPIQ/SUBSPIQ_33") (pintype "passive"))
    )
    (net (code "49") (name "/GPIO38") (class "Default")
      (node (ref "J2") (pin "12") (pinfunction "12_12") (pintype "passive"))
      (node (ref "U1") (pin "34") (pinfunction "GPIO38/FSPIWP/SUBSPIWP_34") (pintype "passive"))
    )
    (net (code "50") (name "/GPIO39") (class "Default")
      (node (ref "J2") (pin "11") (pinfunction "11_11") (pintype "passive"))
      (node (ref "U1") (pin "35") (pinfunction "MTCK/GPIO39/CLK_OUT3/SUBSPICS1_35") (pintype "passive"))
    )
    (net (code "51") (name "/GPIO40") (class "Default")
      (node (ref "J2") (pin "10") (pinfunction "10_10") (pintype "passive"))
      (node (ref "U1") (pin "36") (pinfunction "MTDO/GPIO40/CLK_OUT2_36") (pintype "passive"))
    )
    (net (code "52") (name "/GPIO41") (class "Default")
      (node (ref "J2") (pin "9") (pinfunction "9_9") (pintype "passive"))
      (node (ref "U1") (pin "37") (pinfunction "MTDI/GPIO41/CLK_OUT1_37") (pintype "passive"))
    )
    (net (code "53") (name "/GPIO42") (class "Default")
      (node (ref "J2") (pin "8") (pinfunction "8_8") (pintype "passive"))
      (node (ref "U1") (pin "38") (pinfunction "MTMS,_GPIO42_38") (pintype "passive"))
    )
    (net (code "54") (name "/GPIO45") (class "Default")
      (node (ref "J2") (pin "5") (pinfunction "5_5") (pintype "passive"))
      (node (ref "U1") (pin "41") (pinfunction "GPIO45_41") (pintype "passive"))
    )
    (net (code "55") (name "/GPIO46") (class "Default")
      (node (ref "J2") (pin "4") (pinfunction "4_4") (pintype "passive"))
      (node (ref "U1") (pin "44") (pinfunction "GPIO46_44") (pintype "passive"))
    )
    (net (code "56") (name "/GPIO47") (class "Default")
      (node (ref "J2") (pin "23") (pinfunction "23_23") (pintype "passive"))
      (node (ref "U1") (pin "27") (pinfunction "GPIO47/SPICLK_P_DIFF/SUBSPICLK_P_DIFF_27") (pintype "passive"))
    )
    (net (code "57") (name "/GPIO48") (class "Default")
      (node (ref "J2") (pin "22") (pinfunction "22_22") (pintype "passive"))
      (node (ref "U1") (pin "30") (pinfunction "GPIO48/SPICLK_N_DIFF/SUBSPICLK_N_DIFF_30") (pintype "passive"))
    )
    (net (code "58") (name "/RTS_FTDI") (class "Default")
      (node (ref "Q1") (pin "2") (pinfunction "2_2") (pintype "passive"))
      (node (ref "R18") (pin "2") (pinfunction "2_2") (pintype "passive"))
      (node (ref "U2") (pin "19") (pinfunction "RTS#_19") (pintype "passive"))
    )
    (net (code "59") (name "/RXD_FTDI") (class "Default")
      (node (ref "R17") (pin "2") (pinfunction "2_2") (pintype "passive"))
      (node (ref "U2") (pin "1") (pinfunction "RXD_1") (pintype "passive"))
    )
    (net (code "60") (name "/TXD_FTDI") (class "Default")
      (node (ref "R19") (pin "2") (pinfunction "2_2") (pintype "passive"))
      (node (ref "U2") (pin "17") (pinfunction "TXD_17") (pintype "passive"))
    )
    (net (code "61") (name "/U0RXD") (class "Default")
      (node (ref "J2") (pin "6") (pinfunction "6_6") (pintype "passive"))
      (node (ref "R19") (pin "1") (pinfunction "1_1") (pintype "passive"))
      (node (ref "U1") (pin "40") (pinfunction "U0RXD/_GPIO44/CLK_OUT2_40") (pintype "passive"))
    )
    (net (code "62") (name "/U0TXD") (class "Default")
      (node (ref "J2") (pin "7") (pinfunction "7_7") (pintype "passive"))
      (node (ref "R17") (pin "1") (pinfunction "1_1") (pintype "passive"))
      (node (ref "U1") (pin "39") (pinfunction "U0TXD/GPIO43/CLK_OUT1_39") (pintype "passive"))
    )
    (net (code "63") (name "/VBUS_SENSE") (class "Default")
      (node (ref "R1") (pin "1") (pinfunction "1_1") (pintype "passive"))
      (node (ref "R2") (pin "2") (pinfunction "2_2") (pintype "passive"))
      (node (ref "U2") (pin "16") (pinfunction "CBUS3_16") (pintype "passive"))
    )
    (net (code "64") (name "GND") (class "Default")
      (node (ref "C1") (pin "1") (pinfunction "1_1") (pintype "passive"))
      (node (ref "C10") (pin "1") (pinfunction "1_1") (pintype "passive"))
      (node (ref "C11") (pin "1") (pinfunction "1_1") (pintype "passive"))
      (node (ref "C12") (pin "1") (pinfunction "1_1") (pintype "passive"))
      (node (ref "C13") (pin "1") (pinfunction "1_1") (pintype "passive"))
      (node (ref "C14") (pin "1") (pinfunction "1_1") (pintype "passive"))
      (node (ref "C15") (pin "1") (pinfunction "1_1") (pintype "passive"))
      (node (ref "C16") (pin "1") (pinfunction "1_1") (pintype "passive"))
      (node (ref "C17") (pin "1") (pinfunction "1_1") (pintype "passive"))
      (node (ref "C2") (pin "1") (pinfunction "1_1") (pintype "passive"))
      (node (ref "C3") (pin "1") (pinfunction "1_1") (pintype "passive"))
      (node (ref "C4") (pin "1") (pinfunction "1_1") (pintype "passive"))
      (node (ref "C5") (pin "1") (pinfunction "1_1") (pintype "passive"))
      (node (ref "C6") (pin "1") (pinfunction "1_1") (pintype "passive"))
      (node (ref "C7") (pin "1") (pinfunction "1_1") (pintype "passive"))
      (node (ref "C8") (pin "1") (pinfunction "1_1") (pintype "passive"))
      (node (ref "C9") (pin "1") (pinfunction "1_1") (pintype "passive"))
      (node (ref "D1") (pin "1") (pinfunction "1_1") (pintype "passive"))
      (node (ref "D3") (pin "1") (pinfunction "1_1") (pintype "passive"))
      (node (ref "D4") (pin "1") (pinfunction "1_1") (pintype "passive"))
      (node (ref "D5") (pin "1") (pinfunction "1_1") (pintype "passive"))
      (node (ref "D6") (pin "1") (pinfunction "1_1") (pintype "passive"))
      (node (ref "D7") (pin "1") (pinfunction "1_1") (pintype "passive"))
      (node (ref "D8") (pin "1") (pinfunction "1_1") (pintype "passive"))
      (node (ref "J1") (pin "1") (pinfunction "1_1") (pintype "passive"))
      (node (ref "J1") (pin "23") (pinfunction "23_23") (pintype "passive"))
      (node (ref "J2") (pin "2") (pinfunction "2_2") (pintype "passive"))
      (node (ref "J2") (pin "24") (pinfunction "24_24") (pintype "passive"))
      (node (ref "J3") (pin "A1B12") (pinfunction "GND_A1B12_A1B12") (pintype "passive"))
      (node (ref "J3") (pin "B1A12") (pinfunction "GND_B1A12_B1A12") (pintype "passive"))
      (node (ref "J3") (pin "S1") (pinfunction "SHIELD_1_S1") (pintype "passive"))
      (node (ref "J3") (pin "S2") (pinfunction "SHIELD_2_S2") (pintype "passive"))
      (node (ref "J3") (pin "S3") (pinfunction "SHIELD_3_S3") (pintype "passive"))
      (node (ref "J3") (pin "S4") (pinfunction "SHIELD_4_S4") (pintype "passive"))
      (node (ref "J4") (pin "A1B12") (pinfunction "GND_A1B12_A1B12") (pintype "passive"))
      (node (ref "J4") (pin "B1A12") (pinfunction "GND_B1A12_B1A12") (pintype "passive"))
      (node (ref "J4") (pin "S1") (pinfunction "SHIELD_1_S1") (pintype "passive"))
      (node (ref "J4") (pin "S2") (pinfunction "SHIELD_2_S2") (pintype "passive"))
      (node (ref "J4") (pin "S3") (pinfunction "SHIELD_3_S3") (pintype "passive"))
      (node (ref "J4") (pin "S4") (pinfunction "SHIELD_4_S4") (pintype "passive"))
      (node (ref "R12") (pin "1") (pinfunction "1_1") (pintype "passive"))
      (node (ref "R13") (pin "1") (pinfunction "1_1") (pintype "passive"))
      (node (ref "R14") (pin "1") (pinfunction "1_1") (pintype "passive"))
      (node (ref "R15") (pin "1") (pinfunction "1_1") (pintype "passive"))
      (node (ref "R2") (pin "1") (pinfunction "1_1") (pintype "passive"))
      (node (ref "R7") (pin "2") (pinfunction "2_2") (pintype "passive"))
      (node (ref "SW1") (pin "3") (pinfunction "3_3") (pintype "passive"))
      (node (ref "SW1") (pin "4") (pinfunction "4_4") (pintype "passive"))
      (node (ref "SW2") (pin "3") (pinfunction "3_3") (pintype "passive"))
      (node (ref "SW2") (pin "4") (pinfunction "4_4") (pintype "passive"))
      (node (ref "U1") (pin "1") (pinfunction "GND_1_1") (pintype "passive"))
      (node (ref "U1") (pin "2") (pinfunction "GND_2_2") (pintype "passive"))
      (node (ref "U1") (pin "42") (pinfunction "GND_42") (pintype "passive"))
      (node (ref "U1") (pin "43") (pinfunction "GND_43") (pintype "passive"))
      (node (ref "U1") (pin "46") (pinfunction "GND_46_46") (pintype "passive"))
      (node (ref "U1") (pin "47") (pinfunction "GND_47_47") (pintype "passive"))
      (node (ref "U1") (pin "48") (pinfunction "GND_48_48") (pintype "passive"))
      (node (ref "U1") (pin "49") (pinfunction "GND_49_49") (pintype "passive"))
      (node (ref "U1") (pin "50") (pinfunction "GND_50_50") (pintype "passive"))
      (node (ref "U1") (pin "51") (pinfunction "GND_51_51") (pintype "passive"))
      (node (ref "U1") (pin "52") (pinfunction "GND_52_52") (pintype "passive"))
      (node (ref "U1") (pin "53") (pinfunction "GND_53_53") (pintype "passive"))
      (node (ref "U1") (pin "54") (pinfunction "GND_54_54") (pintype "passive"))
      (node (ref "U1") (pin "55") (pinfunction "GND_55_55") (pintype "passive"))
      (node (ref "U1") (pin "56") (pinfunction "GND_56_56") (pintype "passive"))
      (node (ref "U1") (pin "57") (pinfunction "GND_57_57") (pintype "passive"))
      (node (ref "U1") (pin "58") (pinfunction "GND_58_58") (pintype "passive"))
      (node (ref "U1") (pin "59") (pinfunction "GND_59_59") (pintype "passive"))
      (node (ref "U1") (pin "60") (pinfunction "GND_60_60") (pintype "passive"))
      (node (ref "U1") (pin "61") (pinfunction "GND_61_61") (pintype "passive"))
      (node (ref "U1") (pin "62") (pinfunction "GND_62_62") (pintype "passive"))
      (node (ref "U1") (pin "63") (pinfunction "GND_63_63") (pintype "passive"))
      (node (ref "U1") (pin "64") (pinfunction "GND_64_64") (pintype "passive"))
      (node (ref "U1") (pin "65") (pinfunction "GND_65_65") (pintype "passive"))
      (node (ref "U1") (pin "66") (pinfunction "GND_66_66") (pintype "passive"))
      (node (ref "U1") (pin "67") (pinfunction "GND_67_67") (pintype "passive"))
      (node (ref "U1") (pin "68") (pinfunction "GND_68_68") (pintype "passive"))
      (node (ref "U1") (pin "69") (pinfunction "GND_69_69") (pintype "passive"))
      (node (ref "U1") (pin "70") (pinfunction "GND_70_70") (pintype "passive"))
      (node (ref "U1") (pin "71") (pinfunction "GND_71_71") (pintype "passive"))
      (node (ref "U1") (pin "72") (pinfunction "GND_72_72") (pintype "passive"))
      (node (ref "U1") (pin "73") (pinfunction "GND_73_73") (pintype "passive"))
      (node (ref "U2") (pin "13") (pinfunction "GND_13") (pintype "passive"))
      (node (ref "U2") (pin "21") (pinfunction "GND_21") (pintype "passive"))
      (node (ref "U2") (pin "3") (pinfunction "GND_3") (pintype "passive"))
      (node (ref "U3") (pin "2") (pinfunction "GND_2_2") (pintype "power_in"))
      (node (ref "U3") (pin "4") (pinfunction "GND_4_4") (pintype "power_in"))
    )
    (net (code "65") (name "Net-(D1-Pad2)") (class "Default")
      (node (ref "D1") (pin "2") (pinfunction "2_2") (pintype "passive"))
      (node (ref "R4") (pin "1") (pinfunction "1_1") (pintype "passive"))
    )
    (net (code "66") (name "Net-(D2-Pad2)") (class "Default")
      (node (ref "D2") (pin "2") (pinfunction "2_2") (pintype "passive"))
      (node (ref "R5") (pin "1") (pinfunction "1_1") (pintype "passive"))
    )
    (net (code "67") (name "Net-(J3-CC1)") (class "Default")
      (node (ref "J3") (pin "A5") (pinfunction "CC1_A5") (pintype "passive"))
      (node (ref "R13") (pin "2") (pinfunction "2_2") (pintype "passive"))
    )
    (net (code "68") (name "Net-(J3-CC2)") (class "Default")
      (node (ref "J3") (pin "B5") (pinfunction "CC2_B5") (pintype "passive"))
      (node (ref "R12") (pin "2") (pinfunction "2_2") (pintype "passive"))
    )
    (net (code "69") (name "Net-(J4-CC1)") (class "Default")
      (node (ref "J4") (pin "A5") (pinfunction "CC1_A5") (pintype "passive"))
      (node (ref "R15") (pin "2") (pinfunction "2_2") (pintype "passive"))
    )
    (net (code "70") (name "Net-(J4-CC2)") (class "Default")
      (node (ref "J4") (pin "B5") (pinfunction "CC2_B5") (pintype "passive"))
      (node (ref "R14") (pin "2") (pinfunction "2_2") (pintype "passive"))
    )
    (net (code "71") (name "Net-(Q1-Pad1)") (class "Default")
      (node (ref "Q1") (pin "1") (pinfunction "1_1") (pintype "passive"))
      (node (ref "R16") (pin "1") (pinfunction "1_1") (pintype "passive"))
    )
    (net (code "72") (name "Net-(Q2-Pad1)") (class "Default")
      (node (ref "Q2") (pin "1") (pinfunction "1_1") (pintype "passive"))
      (node (ref "R18") (pin "1") (pinfunction "1_1") (pintype "passive"))
    )
    (net (code "73") (name "Net-(U2-CBUS0)") (class "Default")
      (node (ref "R7") (pin "1") (pinfunction "1_1") (pintype "passive"))
      (node (ref "U2") (pin "15") (pinfunction "CBUS0_15") (pintype "passive"))
    )
    (net (code "74") (name "unconnected-(J1-Pad24)") (class "Default")
      (node (ref "J1") (pin "24") (pinfunction "24_24") (pintype "passive+no_connect"))
    )
    (net (code "75") (name "unconnected-(J3-SBU1-PadA8)") (class "Default")
      (node (ref "J3") (pin "A8") (pinfunction "SBU1_A8") (pintype "passive+no_connect"))
    )
    (net (code "76") (name "unconnected-(J3-SBU2-PadB8)") (class "Default")
      (node (ref "J3") (pin "B8") (pinfunction "SBU2_B8") (pintype "passive+no_connect"))
    )
    (net (code "77") (name "unconnected-(J4-SBU1-PadA8)") (class "Default")
      (node (ref "J4") (pin "A8") (pinfunction "SBU1_A8") (pintype "passive+no_connect"))
    )
    (net (code "78") (name "unconnected-(J4-SBU2-PadB8)") (class "Default")
      (node (ref "J4") (pin "B8") (pinfunction "SBU2_B8") (pintype "passive+no_connect"))
    )
    (net (code "79") (name "unconnected-(U2-CBUS1-Pad14)") (class "Default")
      (node (ref "U2") (pin "14") (pinfunction "CBUS1_14") (pintype "passive+no_connect"))
    )
    (net (code "80") (name "unconnected-(U2-CBUS2-Pad7)") (class "Default")
      (node (ref "U2") (pin "7") (pinfunction "CBUS2_7") (pintype "passive+no_connect"))
    )
    (net (code "81") (name "unconnected-(U2-CTS#-Pad6)") (class "Default")
      (node (ref "U2") (pin "6") (pinfunction "CTS#_6") (pintype "passive+no_connect"))
    )
    (net (code "82") (name "unconnected-(U2-DCD#-Pad5)") (class "Default")
      (node (ref "U2") (pin "5") (pinfunction "DCD#_5") (pintype "passive+no_connect"))
    )
    (net (code "83") (name "unconnected-(U2-DSR#-Pad4)") (class "Default")
      (node (ref "U2") (pin "4") (pinfunction "DSR#_4") (pintype "passive+no_connect"))
    )
    (net (code "84") (name "unconnected-(U2-RI#-Pad2)") (class "Default")
      (node (ref "U2") (pin "2") (pinfunction "RI#_2") (pintype "passive+no_connect"))
    )
  )
)
